# Simon_Says_Jump.net
KiCad netlist of a schematic drawn in EAGLE
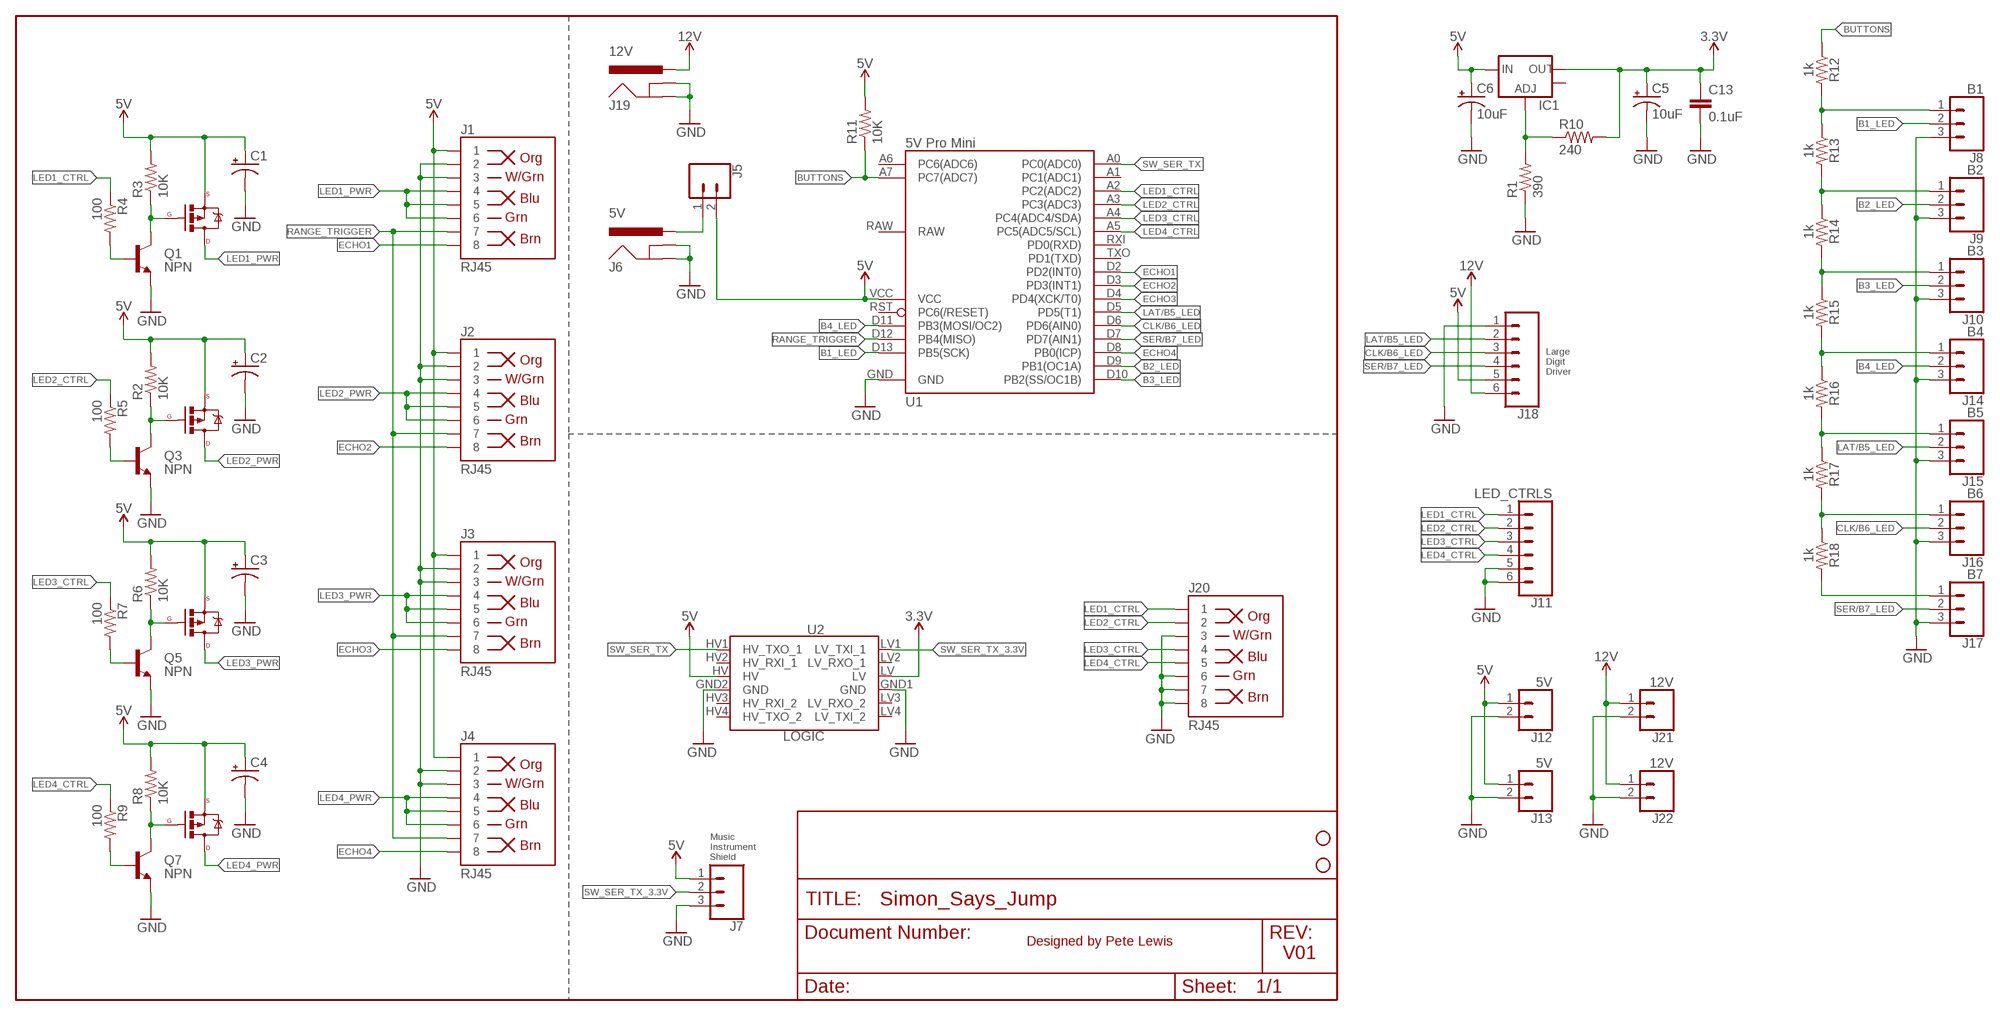
[diagram p0: schematic, sheet 1]

(export (version "E")
  (design (tool "Eeschema 10.0.6"))
  (components
    (comp (ref "C1")
      (value "CAP_POLCPOL-RADIAL-10UF-25V-KIT")
      (footprint "eagle-import:CPOL-RADIAL-10UF-25V-KIT")
      (libsource (lib "eagle-import") (part "CAP_POLCPOL-RADIAL-10UF-25V-KIT"))
    )
    (comp (ref "C2")
      (value "CAP_POLCPOL-RADIAL-10UF-25V-KIT")
      (footprint "eagle-import:CPOL-RADIAL-10UF-25V-KIT")
      (libsource (lib "eagle-import") (part "CAP_POLCPOL-RADIAL-10UF-25V-KIT"))
    )
    (comp (ref "C3")
      (value "CAP_POLCPOL-RADIAL-10UF-25V-KIT")
      (footprint "eagle-import:CPOL-RADIAL-10UF-25V-KIT")
      (libsource (lib "eagle-import") (part "CAP_POLCPOL-RADIAL-10UF-25V-KIT"))
    )
    (comp (ref "C4")
      (value "CAP_POLCPOL-RADIAL-10UF-25V-KIT")
      (footprint "eagle-import:CPOL-RADIAL-10UF-25V-KIT")
      (libsource (lib "eagle-import") (part "CAP_POLCPOL-RADIAL-10UF-25V-KIT"))
    )
    (comp (ref "C5")
      (value "10uF")
      (footprint "eagle-import:EIA3216")
      (libsource (lib "eagle-import") (part "CAP_POL1206"))
    )
    (comp (ref "C6")
      (value "10uF")
      (footprint "eagle-import:EIA3216")
      (libsource (lib "eagle-import") (part "CAP_POL1206"))
    )
    (comp (ref "C13")
      (value "0.1uF")
      (footprint "eagle-import:0603-CAP")
      (libsource (lib "eagle-import") (part "CAP0603-CAP"))
    )
    (comp (ref "IC1")
      (value "V_REG_LM1117SOT223")
      (footprint "eagle-import:SOT223")
      (libsource (lib "eagle-import") (part "V_REG_LM1117SOT223"))
    )
    (comp (ref "J1")
      (value "RJ45")
      (footprint "eagle-import:RJ45-8")
      (libsource (lib "eagle-import") (part "RJ45-8"))
    )
    (comp (ref "J2")
      (value "RJ45")
      (footprint "eagle-import:RJ45-8")
      (libsource (lib "eagle-import") (part "RJ45-8"))
    )
    (comp (ref "J3")
      (value "RJ45")
      (footprint "eagle-import:RJ45-8")
      (libsource (lib "eagle-import") (part "RJ45-8"))
    )
    (comp (ref "J4")
      (value "RJ45")
      (footprint "eagle-import:RJ45-8")
      (libsource (lib "eagle-import") (part "RJ45-8"))
    )
    (comp (ref "J5")
      (value "CONN_02PTH3")
      (footprint "eagle-import:1X02_LONGPADS")
      (libsource (lib "eagle-import") (part "CONN_02PTH3"))
    )
    (comp (ref "J6")
      (value "5V")
      (footprint "eagle-import:POWER_JACK_PTH_LOCK")
      (libsource (lib "eagle-import") (part "POWER_JACKPTH_LOCK"))
    )
    (comp (ref "J7")
      (value "CONN_03LONGPADS")
      (footprint "eagle-import:1X03_LONGPADS")
      (libsource (lib "eagle-import") (part "CONN_03LONGPADS"))
    )
    (comp (ref "J8")
      (value "B1")
      (footprint "eagle-import:1X03_LONGPADS")
      (libsource (lib "eagle-import") (part "CONN_03LONGPADS"))
    )
    (comp (ref "J9")
      (value "B2")
      (footprint "eagle-import:1X03_LONGPADS")
      (libsource (lib "eagle-import") (part "CONN_03LONGPADS"))
    )
    (comp (ref "J10")
      (value "B3")
      (footprint "eagle-import:1X03_LONGPADS")
      (libsource (lib "eagle-import") (part "CONN_03LONGPADS"))
    )
    (comp (ref "J11")
      (value "LED_CTRLS")
      (footprint "eagle-import:1X06_LONGPADS")
      (libsource (lib "eagle-import") (part "CONN_06LONGPADS"))
    )
    (comp (ref "J12")
      (value "5V")
      (footprint "eagle-import:1X02_LONGPADS")
      (libsource (lib "eagle-import") (part "CONN_02PTH3"))
    )
    (comp (ref "J13")
      (value "5V")
      (footprint "eagle-import:1X02_LONGPADS")
      (libsource (lib "eagle-import") (part "CONN_02PTH3"))
    )
    (comp (ref "J14")
      (value "B4")
      (footprint "eagle-import:1X03_LONGPADS")
      (libsource (lib "eagle-import") (part "CONN_03LONGPADS"))
    )
    (comp (ref "J15")
      (value "B5")
      (footprint "eagle-import:1X03_LONGPADS")
      (libsource (lib "eagle-import") (part "CONN_03LONGPADS"))
    )
    (comp (ref "J16")
      (value "B6")
      (footprint "eagle-import:1X03_LONGPADS")
      (libsource (lib "eagle-import") (part "CONN_03LONGPADS"))
    )
    (comp (ref "J17")
      (value "B7")
      (footprint "eagle-import:1X03_LONGPADS")
      (libsource (lib "eagle-import") (part "CONN_03LONGPADS"))
    )
    (comp (ref "J18")
      (value "CONN_06LONGPADS")
      (footprint "eagle-import:1X06_LONGPADS")
      (libsource (lib "eagle-import") (part "CONN_06LONGPADS"))
    )
    (comp (ref "J19")
      (value "12V")
      (footprint "eagle-import:POWER_JACK_PTH_LOCK")
      (libsource (lib "eagle-import") (part "POWER_JACKPTH_LOCK"))
    )
    (comp (ref "J20")
      (value "RJ45")
      (footprint "eagle-import:RJ45-8")
      (libsource (lib "eagle-import") (part "RJ45-8"))
    )
    (comp (ref "J21")
      (value "12V")
      (footprint "eagle-import:1X02_LONGPADS")
      (libsource (lib "eagle-import") (part "CONN_02PTH3"))
    )
    (comp (ref "J22")
      (value "12V")
      (footprint "eagle-import:1X02_LONGPADS")
      (libsource (lib "eagle-import") (part "CONN_02PTH3"))
    )
    (comp (ref "JP1")
      (value "STAND-OFFTIGHTER")
      (footprint "eagle-import:STAND-OFF-TIGHTER")
      (libsource (lib "eagle-import") (part "STAND-OFFTIGHTER"))
    )
    (comp (ref "JP7")
      (value "STAND-OFFTIGHTER")
      (footprint "eagle-import:STAND-OFF-TIGHTER")
      (libsource (lib "eagle-import") (part "STAND-OFFTIGHTER"))
    )
    (comp (ref "Q1")
      (value "NPN")
      (footprint "eagle-import:SOT23")
      (libsource (lib "eagle-import") (part "TRANSISTOR_NPNSOT23"))
    )
    (comp (ref "Q2")
      (value "P-Channel MOSFET")
      (footprint "eagle-import:TO220V")
      (libsource (lib "eagle-import") (part "MOSFET-PCHANNELPTH"))
    )
    (comp (ref "Q3")
      (value "NPN")
      (footprint "eagle-import:SOT23")
      (libsource (lib "eagle-import") (part "TRANSISTOR_NPNSOT23"))
    )
    (comp (ref "Q4")
      (value "P-Channel MOSFET")
      (footprint "eagle-import:TO220V")
      (libsource (lib "eagle-import") (part "MOSFET-PCHANNELPTH"))
    )
    (comp (ref "Q5")
      (value "NPN")
      (footprint "eagle-import:SOT23")
      (libsource (lib "eagle-import") (part "TRANSISTOR_NPNSOT23"))
    )
    (comp (ref "Q6")
      (value "P-Channel MOSFET")
      (footprint "eagle-import:TO220V")
      (libsource (lib "eagle-import") (part "MOSFET-PCHANNELPTH"))
    )
    (comp (ref "Q7")
      (value "NPN")
      (footprint "eagle-import:SOT23")
      (libsource (lib "eagle-import") (part "TRANSISTOR_NPNSOT23"))
    )
    (comp (ref "Q8")
      (value "P-Channel MOSFET")
      (footprint "eagle-import:TO220V")
      (libsource (lib "eagle-import") (part "MOSFET-PCHANNELPTH"))
    )
    (comp (ref "R1")
      (value "390")
      (footprint "eagle-import:0603-RES")
      (libsource (lib "eagle-import") (part "RESISTOR0603-RES"))
    )
    (comp (ref "R2")
      (value "10K")
      (footprint "eagle-import:0603-RES")
      (libsource (lib "eagle-import") (part "RESISTOR0603-RES"))
    )
    (comp (ref "R3")
      (value "10K")
      (footprint "eagle-import:0603-RES")
      (libsource (lib "eagle-import") (part "RESISTOR0603-RES"))
    )
    (comp (ref "R4")
      (value "100")
      (footprint "eagle-import:0603-RES")
      (libsource (lib "eagle-import") (part "RESISTOR0603-RES"))
    )
    (comp (ref "R5")
      (value "100")
      (footprint "eagle-import:0603-RES")
      (libsource (lib "eagle-import") (part "RESISTOR0603-RES"))
    )
    (comp (ref "R6")
      (value "10K")
      (footprint "eagle-import:0603-RES")
      (libsource (lib "eagle-import") (part "RESISTOR0603-RES"))
    )
    (comp (ref "R7")
      (value "100")
      (footprint "eagle-import:0603-RES")
      (libsource (lib "eagle-import") (part "RESISTOR0603-RES"))
    )
    (comp (ref "R8")
      (value "10K")
      (footprint "eagle-import:0603-RES")
      (libsource (lib "eagle-import") (part "RESISTOR0603-RES"))
    )
    (comp (ref "R9")
      (value "100")
      (footprint "eagle-import:0603-RES")
      (libsource (lib "eagle-import") (part "RESISTOR0603-RES"))
    )
    (comp (ref "R10")
      (value "240")
      (footprint "eagle-import:0603-RES")
      (libsource (lib "eagle-import") (part "RESISTOR0603-RES"))
    )
    (comp (ref "R11")
      (value "10K")
      (footprint "eagle-import:0603-RES")
      (libsource (lib "eagle-import") (part "RESISTOR0603-RES"))
    )
    (comp (ref "R12")
      (value "1k")
      (footprint "eagle-import:0603")
      (libsource (lib "eagle-import") (part "1KOHM-0603-1/10W-1%"))
    )
    (comp (ref "R13")
      (value "1k")
      (footprint "eagle-import:0603")
      (libsource (lib "eagle-import") (part "1KOHM-0603-1/10W-1%"))
    )
    (comp (ref "R14")
      (value "1k")
      (footprint "eagle-import:0603")
      (libsource (lib "eagle-import") (part "1KOHM-0603-1/10W-1%"))
    )
    (comp (ref "R15")
      (value "1k")
      (footprint "eagle-import:0603")
      (libsource (lib "eagle-import") (part "1KOHM-0603-1/10W-1%"))
    )
    (comp (ref "R16")
      (value "1k")
      (footprint "eagle-import:0603")
      (libsource (lib "eagle-import") (part "1KOHM-0603-1/10W-1%"))
    )
    (comp (ref "R17")
      (value "1k")
      (footprint "eagle-import:0603")
      (libsource (lib "eagle-import") (part "1KOHM-0603-1/10W-1%"))
    )
    (comp (ref "R18")
      (value "1k")
      (footprint "eagle-import:0603")
      (libsource (lib "eagle-import") (part "1KOHM-0603-1/10W-1%"))
    )
    (comp (ref "U1")
      (value "5V Pro Mini")
      (footprint "eagle-import:ARDUINO_PRO_MINI-V13_DIP")
      (libsource (lib "eagle-import") (part "ARDUINO_PRO_MINI-V13-DIP"))
    )
    (comp (ref "U2")
      (value "LOGIC")
      (footprint "eagle-import:SPARKFUN_LOGIC_LEVEL_CONVERTER")
      (libsource (lib "eagle-import") (part "SPARKFUN_LOGIC_LEVEL_CONVERTER"))
    )
  )
  (nets
    (net (code "1") (name "3.3V") (class "Default")
      (node (ref "C13") (pin "1") (pinfunction "1_1") (pintype "passive"))
      (node (ref "C5") (pin "A") (pinfunction "+_A") (pintype "passive"))
      (node (ref "IC1") (pin "2") (pinfunction "OUT_2") (pintype "output"))
      (node (ref "R10") (pin "2") (pinfunction "2_2") (pintype "passive"))
      (node (ref "U2") (pin "LV") (pinfunction "LV_LV") (pintype "power_in"))
    )
    (net (code "2") (name "5V") (class "Default")
      (node (ref "C1") (pin "1") (pinfunction "+_1") (pintype "passive"))
      (node (ref "C2") (pin "1") (pinfunction "+_1") (pintype "passive"))
      (node (ref "C3") (pin "1") (pinfunction "+_1") (pintype "passive"))
      (node (ref "C4") (pin "1") (pinfunction "+_1") (pintype "passive"))
      (node (ref "C6") (pin "A") (pinfunction "+_A") (pintype "passive"))
      (node (ref "IC1") (pin "3") (pinfunction "IN_3") (pintype "input"))
      (node (ref "J1") (pin "1") (pinfunction "1_1") (pintype "bidirectional"))
      (node (ref "J12") (pin "1") (pinfunction "1_1") (pintype "passive"))
      (node (ref "J13") (pin "1") (pinfunction "1_1") (pintype "passive"))
      (node (ref "J18") (pin "5") (pinfunction "5_5") (pintype "passive"))
      (node (ref "J2") (pin "1") (pinfunction "1_1") (pintype "bidirectional"))
      (node (ref "J3") (pin "1") (pinfunction "1_1") (pintype "bidirectional"))
      (node (ref "J4") (pin "1") (pinfunction "1_1") (pintype "bidirectional"))
      (node (ref "J5") (pin "2") (pinfunction "2_2") (pintype "passive"))
      (node (ref "J7") (pin "1") (pinfunction "1_1") (pintype "passive"))
      (node (ref "Q2") (pin "3") (pinfunction "S_3") (pintype "passive"))
      (node (ref "Q4") (pin "3") (pinfunction "S_3") (pintype "passive"))
      (node (ref "Q6") (pin "3") (pinfunction "S_3") (pintype "passive"))
      (node (ref "Q8") (pin "3") (pinfunction "S_3") (pintype "passive"))
      (node (ref "R11") (pin "2") (pinfunction "2_2") (pintype "passive"))
      (node (ref "R2") (pin "2") (pinfunction "2_2") (pintype "passive"))
      (node (ref "R3") (pin "2") (pinfunction "2_2") (pintype "passive"))
      (node (ref "R6") (pin "2") (pinfunction "2_2") (pintype "passive"))
      (node (ref "R8") (pin "2") (pinfunction "2_2") (pintype "passive"))
      (node (ref "U1") (pin "VCC") (pinfunction "VCC_VCC") (pintype "bidirectional"))
      (node (ref "U2") (pin "HV") (pinfunction "HV_HV") (pintype "power_in"))
    )
    (net (code "3") (name "12V") (class "Default")
      (node (ref "J18") (pin "6") (pinfunction "6_6") (pintype "passive"))
      (node (ref "J19") (pin "PWR") (pinfunction "PWR_PWR") (pintype "bidirectional"))
      (node (ref "J21") (pin "1") (pinfunction "1_1") (pintype "passive"))
      (node (ref "J22") (pin "1") (pinfunction "1_1") (pintype "passive"))
    )
    (net (code "4") (name "B1_LED") (class "Default")
      (node (ref "J8") (pin "2") (pinfunction "2_2") (pintype "passive"))
      (node (ref "U1") (pin "D13") (pinfunction "PB5(SCK)_D13") (pintype "bidirectional"))
    )
    (net (code "5") (name "B2_LED") (class "Default")
      (node (ref "J9") (pin "2") (pinfunction "2_2") (pintype "passive"))
      (node (ref "U1") (pin "D9") (pinfunction "PB1(OC1A)_D9") (pintype "bidirectional"))
    )
    (net (code "6") (name "B3_LED") (class "Default")
      (node (ref "J10") (pin "2") (pinfunction "2_2") (pintype "passive"))
      (node (ref "U1") (pin "D10") (pinfunction "PB2(SS/OC1B)_D10") (pintype "bidirectional"))
    )
    (net (code "7") (name "B4_LED") (class "Default")
      (node (ref "J14") (pin "2") (pinfunction "2_2") (pintype "passive"))
      (node (ref "U1") (pin "D11") (pinfunction "PB3(MOSI/OC2)_D11") (pintype "bidirectional"))
    )
    (net (code "8") (name "BUTTONS") (class "Default")
      (node (ref "R11") (pin "1") (pinfunction "1_1") (pintype "passive"))
      (node (ref "R12") (pin "1") (pinfunction "1_1") (pintype "passive"))
      (node (ref "U1") (pin "A7") (pinfunction "PC7(ADC7)_A7") (pintype "bidirectional"))
    )
    (net (code "9") (name "CLK{slash}B6_LED") (class "Default")
      (node (ref "J16") (pin "2") (pinfunction "2_2") (pintype "passive"))
      (node (ref "J18") (pin "3") (pinfunction "3_3") (pintype "passive"))
      (node (ref "U1") (pin "D6") (pinfunction "PD6(AIN0)_D6") (pintype "bidirectional"))
    )
    (net (code "10") (name "ECHO1") (class "Default")
      (node (ref "J1") (pin "8") (pinfunction "8_8") (pintype "bidirectional"))
      (node (ref "U1") (pin "D2") (pinfunction "PD2(INT0)_D2") (pintype "bidirectional"))
    )
    (net (code "11") (name "ECHO2") (class "Default")
      (node (ref "J2") (pin "8") (pinfunction "8_8") (pintype "bidirectional"))
      (node (ref "U1") (pin "D3") (pinfunction "PD3(INT1)_D3") (pintype "bidirectional"))
    )
    (net (code "12") (name "ECHO3") (class "Default")
      (node (ref "J3") (pin "8") (pinfunction "8_8") (pintype "bidirectional"))
      (node (ref "U1") (pin "D4") (pinfunction "PD4(XCK/T0)_D4") (pintype "bidirectional"))
    )
    (net (code "13") (name "ECHO4") (class "Default")
      (node (ref "J4") (pin "8") (pinfunction "8_8") (pintype "bidirectional"))
      (node (ref "U1") (pin "D8") (pinfunction "PB0(ICP)_D8") (pintype "bidirectional"))
    )
    (net (code "14") (name "GND") (class "Default")
      (node (ref "C1") (pin "2") (pinfunction "-_2") (pintype "passive"))
      (node (ref "C13") (pin "2") (pinfunction "2_2") (pintype "passive"))
      (node (ref "C2") (pin "2") (pinfunction "-_2") (pintype "passive"))
      (node (ref "C3") (pin "2") (pinfunction "-_2") (pintype "passive"))
      (node (ref "C4") (pin "2") (pinfunction "-_2") (pintype "passive"))
      (node (ref "C5") (pin "C") (pinfunction "-_C") (pintype "passive"))
      (node (ref "C6") (pin "C") (pinfunction "-_C") (pintype "passive"))
      (node (ref "J1") (pin "2") (pinfunction "2_2") (pintype "bidirectional"))
      (node (ref "J1") (pin "3") (pinfunction "3_3") (pintype "bidirectional"))
      (node (ref "J10") (pin "3") (pinfunction "3_3") (pintype "passive"))
      (node (ref "J11") (pin "5") (pinfunction "5_5") (pintype "passive"))
      (node (ref "J11") (pin "6") (pinfunction "6_6") (pintype "passive"))
      (node (ref "J12") (pin "2") (pinfunction "2_2") (pintype "passive"))
      (node (ref "J13") (pin "2") (pinfunction "2_2") (pintype "passive"))
      (node (ref "J14") (pin "3") (pinfunction "3_3") (pintype "passive"))
      (node (ref "J15") (pin "3") (pinfunction "3_3") (pintype "passive"))
      (node (ref "J16") (pin "3") (pinfunction "3_3") (pintype "passive"))
      (node (ref "J17") (pin "3") (pinfunction "3_3") (pintype "passive"))
      (node (ref "J18") (pin "1") (pinfunction "1_1") (pintype "passive"))
      (node (ref "J19") (pin "GND") (pinfunction "GND_GND") (pintype "bidirectional"))
      (node (ref "J19") (pin "GNDBREAK") (pinfunction "GNDBREAK_GNDBREAK") (pintype "bidirectional"))
      (node (ref "J2") (pin "2") (pinfunction "2_2") (pintype "bidirectional"))
      (node (ref "J2") (pin "3") (pinfunction "3_3") (pintype "bidirectional"))
      (node (ref "J20") (pin "3") (pinfunction "3_3") (pintype "bidirectional"))
      (node (ref "J20") (pin "6") (pinfunction "6_6") (pintype "bidirectional"))
      (node (ref "J20") (pin "7") (pinfunction "7_7") (pintype "bidirectional"))
      (node (ref "J20") (pin "8") (pinfunction "8_8") (pintype "bidirectional"))
      (node (ref "J21") (pin "2") (pinfunction "2_2") (pintype "passive"))
      (node (ref "J22") (pin "2") (pinfunction "2_2") (pintype "passive"))
      (node (ref "J3") (pin "2") (pinfunction "2_2") (pintype "bidirectional"))
      (node (ref "J3") (pin "3") (pinfunction "3_3") (pintype "bidirectional"))
      (node (ref "J4") (pin "2") (pinfunction "2_2") (pintype "bidirectional"))
      (node (ref "J4") (pin "3") (pinfunction "3_3") (pintype "bidirectional"))
      (node (ref "J6") (pin "GND") (pinfunction "GND_GND") (pintype "bidirectional"))
      (node (ref "J6") (pin "GNDBREAK") (pinfunction "GNDBREAK_GNDBREAK") (pintype "bidirectional"))
      (node (ref "J7") (pin "3") (pinfunction "3_3") (pintype "passive"))
      (node (ref "J8") (pin "3") (pinfunction "3_3") (pintype "passive"))
      (node (ref "J9") (pin "3") (pinfunction "3_3") (pintype "passive"))
      (node (ref "Q1") (pin "2") (pinfunction "E_2") (pintype "passive"))
      (node (ref "Q3") (pin "2") (pinfunction "E_2") (pintype "passive"))
      (node (ref "Q5") (pin "2") (pinfunction "E_2") (pintype "passive"))
      (node (ref "Q7") (pin "2") (pinfunction "E_2") (pintype "passive"))
      (node (ref "R1") (pin "1") (pinfunction "1_1") (pintype "passive"))
      (node (ref "U1") (pin "GND") (pinfunction "GND_GND") (pintype "bidirectional"))
      (node (ref "U2") (pin "GND1") (pinfunction "GND_GND1") (pintype "power_in"))
      (node (ref "U2") (pin "GND2") (pinfunction "GND_GND2") (pintype "power_in"))
    )
    (net (code "15") (name "LAT{slash}B5_LED") (class "Default")
      (node (ref "J15") (pin "2") (pinfunction "2_2") (pintype "passive"))
      (node (ref "J18") (pin "2") (pinfunction "2_2") (pintype "passive"))
      (node (ref "U1") (pin "D5") (pinfunction "PD5(T1)_D5") (pintype "bidirectional"))
    )
    (net (code "16") (name "LED1_CTRL") (class "Default")
      (node (ref "J11") (pin "1") (pinfunction "1_1") (pintype "passive"))
      (node (ref "J20") (pin "1") (pinfunction "1_1") (pintype "bidirectional"))
      (node (ref "R4") (pin "1") (pinfunction "1_1") (pintype "passive"))
      (node (ref "U1") (pin "A2") (pinfunction "PC2(ADC2)_A2") (pintype "bidirectional"))
    )
    (net (code "17") (name "LED1_PWR") (class "Default")
      (node (ref "J1") (pin "4") (pinfunction "4_4") (pintype "bidirectional"))
      (node (ref "J1") (pin "5") (pinfunction "5_5") (pintype "bidirectional"))
      (node (ref "J1") (pin "6") (pinfunction "6_6") (pintype "bidirectional"))
      (node (ref "Q2") (pin "2") (pinfunction "D_2") (pintype "passive"))
    )
    (net (code "18") (name "LED2_CTRL") (class "Default")
      (node (ref "J11") (pin "2") (pinfunction "2_2") (pintype "passive"))
      (node (ref "J20") (pin "2") (pinfunction "2_2") (pintype "bidirectional"))
      (node (ref "R5") (pin "1") (pinfunction "1_1") (pintype "passive"))
      (node (ref "U1") (pin "A3") (pinfunction "PC3(ADC3)_A3") (pintype "bidirectional"))
    )
    (net (code "19") (name "LED2_PWR") (class "Default")
      (node (ref "J2") (pin "4") (pinfunction "4_4") (pintype "bidirectional"))
      (node (ref "J2") (pin "5") (pinfunction "5_5") (pintype "bidirectional"))
      (node (ref "J2") (pin "6") (pinfunction "6_6") (pintype "bidirectional"))
      (node (ref "Q4") (pin "2") (pinfunction "D_2") (pintype "passive"))
    )
    (net (code "20") (name "LED3_CTRL") (class "Default")
      (node (ref "J11") (pin "3") (pinfunction "3_3") (pintype "passive"))
      (node (ref "J20") (pin "4") (pinfunction "4_4") (pintype "bidirectional"))
      (node (ref "R7") (pin "1") (pinfunction "1_1") (pintype "passive"))
      (node (ref "U1") (pin "A4") (pinfunction "PC4(ADC4/SDA)_A4") (pintype "bidirectional"))
    )
    (net (code "21") (name "LED3_PWR") (class "Default")
      (node (ref "J3") (pin "4") (pinfunction "4_4") (pintype "bidirectional"))
      (node (ref "J3") (pin "5") (pinfunction "5_5") (pintype "bidirectional"))
      (node (ref "J3") (pin "6") (pinfunction "6_6") (pintype "bidirectional"))
      (node (ref "Q6") (pin "2") (pinfunction "D_2") (pintype "passive"))
    )
    (net (code "22") (name "LED4_CTRL") (class "Default")
      (node (ref "J11") (pin "4") (pinfunction "4_4") (pintype "passive"))
      (node (ref "J20") (pin "5") (pinfunction "5_5") (pintype "bidirectional"))
      (node (ref "R9") (pin "1") (pinfunction "1_1") (pintype "passive"))
      (node (ref "U1") (pin "A5") (pinfunction "PC5(ADC5/SCL)_A5") (pintype "bidirectional"))
    )
    (net (code "23") (name "LED4_PWR") (class "Default")
      (node (ref "J4") (pin "4") (pinfunction "4_4") (pintype "bidirectional"))
      (node (ref "J4") (pin "5") (pinfunction "5_5") (pintype "bidirectional"))
      (node (ref "J4") (pin "6") (pinfunction "6_6") (pintype "bidirectional"))
      (node (ref "Q8") (pin "2") (pinfunction "D_2") (pintype "passive"))
    )
    (net (code "24") (name "Net-(IC1-ADJ)") (class "Default")
      (node (ref "IC1") (pin "1") (pinfunction "ADJ_1") (pintype "input"))
      (node (ref "R1") (pin "2") (pinfunction "2_2") (pintype "passive"))
      (node (ref "R10") (pin "1") (pinfunction "1_1") (pintype "passive"))
    )
    (net (code "25") (name "Net-(J5-Pad1)") (class "Default")
      (node (ref "J5") (pin "1") (pinfunction "1_1") (pintype "passive"))
      (node (ref "J6") (pin "PWR") (pinfunction "PWR_PWR") (pintype "bidirectional"))
    )
    (net (code "26") (name "Net-(J8-Pad1)") (class "Default")
      (node (ref "J8") (pin "1") (pinfunction "1_1") (pintype "passive"))
      (node (ref "R12") (pin "2") (pinfunction "2_2") (pintype "passive"))
      (node (ref "R13") (pin "1") (pinfunction "1_1") (pintype "passive"))
    )
    (net (code "27") (name "Net-(J9-Pad1)") (class "Default")
      (node (ref "J9") (pin "1") (pinfunction "1_1") (pintype "passive"))
      (node (ref "R13") (pin "2") (pinfunction "2_2") (pintype "passive"))
      (node (ref "R14") (pin "1") (pinfunction "1_1") (pintype "passive"))
    )
    (net (code "28") (name "Net-(J10-Pad1)") (class "Default")
      (node (ref "J10") (pin "1") (pinfunction "1_1") (pintype "passive"))
      (node (ref "R14") (pin "2") (pinfunction "2_2") (pintype "passive"))
      (node (ref "R15") (pin "1") (pinfunction "1_1") (pintype "passive"))
    )
    (net (code "29") (name "Net-(J14-Pad1)") (class "Default")
      (node (ref "J14") (pin "1") (pinfunction "1_1") (pintype "passive"))
      (node (ref "R15") (pin "2") (pinfunction "2_2") (pintype "passive"))
      (node (ref "R16") (pin "1") (pinfunction "1_1") (pintype "passive"))
    )
    (net (code "30") (name "Net-(J15-Pad1)") (class "Default")
      (node (ref "J15") (pin "1") (pinfunction "1_1") (pintype "passive"))
      (node (ref "R16") (pin "2") (pinfunction "2_2") (pintype "passive"))
      (node (ref "R17") (pin "1") (pinfunction "1_1") (pintype "passive"))
    )
    (net (code "31") (name "Net-(J16-Pad1)") (class "Default")
      (node (ref "J16") (pin "1") (pinfunction "1_1") (pintype "passive"))
      (node (ref "R17") (pin "2") (pinfunction "2_2") (pintype "passive"))
      (node (ref "R18") (pin "1") (pinfunction "1_1") (pintype "passive"))
    )
    (net (code "32") (name "Net-(J17-Pad1)") (class "Default")
      (node (ref "J17") (pin "1") (pinfunction "1_1") (pintype "passive"))
      (node (ref "R18") (pin "2") (pinfunction "2_2") (pintype "passive"))
    )
    (net (code "33") (name "Net-(Q1-B)") (class "Default")
      (node (ref "Q1") (pin "1") (pinfunction "B_1") (pintype "passive"))
      (node (ref "R4") (pin "2") (pinfunction "2_2") (pintype "passive"))
    )
    (net (code "34") (name "Net-(Q1-C)") (class "Default")
      (node (ref "Q1") (pin "3") (pinfunction "C_3") (pintype "passive"))
      (node (ref "Q2") (pin "1") (pinfunction "G_1") (pintype "passive"))
      (node (ref "R3") (pin "1") (pinfunction "1_1") (pintype "passive"))
    )
    (net (code "35") (name "Net-(Q3-B)") (class "Default")
      (node (ref "Q3") (pin "1") (pinfunction "B_1") (pintype "passive"))
      (node (ref "R5") (pin "2") (pinfunction "2_2") (pintype "passive"))
    )
    (net (code "36") (name "Net-(Q3-C)") (class "Default")
      (node (ref "Q3") (pin "3") (pinfunction "C_3") (pintype "passive"))
      (node (ref "Q4") (pin "1") (pinfunction "G_1") (pintype "passive"))
      (node (ref "R2") (pin "1") (pinfunction "1_1") (pintype "passive"))
    )
    (net (code "37") (name "Net-(Q5-B)") (class "Default")
      (node (ref "Q5") (pin "1") (pinfunction "B_1") (pintype "passive"))
      (node (ref "R7") (pin "2") (pinfunction "2_2") (pintype "passive"))
    )
    (net (code "38") (name "Net-(Q5-C)") (class "Default")
      (node (ref "Q5") (pin "3") (pinfunction "C_3") (pintype "passive"))
      (node (ref "Q6") (pin "1") (pinfunction "G_1") (pintype "passive"))
      (node (ref "R6") (pin "1") (pinfunction "1_1") (pintype "passive"))
    )
    (net (code "39") (name "Net-(Q7-B)") (class "Default")
      (node (ref "Q7") (pin "1") (pinfunction "B_1") (pintype "passive"))
      (node (ref "R9") (pin "2") (pinfunction "2_2") (pintype "passive"))
    )
    (net (code "40") (name "Net-(Q7-C)") (class "Default")
      (node (ref "Q7") (pin "3") (pinfunction "C_3") (pintype "passive"))
      (node (ref "Q8") (pin "1") (pinfunction "G_1") (pintype "passive"))
      (node (ref "R8") (pin "1") (pinfunction "1_1") (pintype "passive"))
    )
    (net (code "41") (name "RANGE_TRIGGER") (class "Default")
      (node (ref "J1") (pin "7") (pinfunction "7_7") (pintype "bidirectional"))
      (node (ref "J2") (pin "7") (pinfunction "7_7") (pintype "bidirectional"))
      (node (ref "J3") (pin "7") (pinfunction "7_7") (pintype "bidirectional"))
      (node (ref "J4") (pin "7") (pinfunction "7_7") (pintype "bidirectional"))
      (node (ref "U1") (pin "D12") (pinfunction "PB4(MISO)_D12") (pintype "bidirectional"))
    )
    (net (code "42") (name "SER{slash}B7_LED") (class "Default")
      (node (ref "J17") (pin "2") (pinfunction "2_2") (pintype "passive"))
      (node (ref "J18") (pin "4") (pinfunction "4_4") (pintype "passive"))
      (node (ref "U1") (pin "D7") (pinfunction "PD7(AIN1)_D7") (pintype "bidirectional"))
    )
    (net (code "43") (name "SW_SER_TX") (class "Default")
      (node (ref "U1") (pin "A0") (pinfunction "PC0(ADC0)_A0") (pintype "bidirectional"))
      (node (ref "U2") (pin "HV1") (pinfunction "HV_TXO_1_HV1") (pintype "bidirectional"))
    )
    (net (code "44") (name "SW_SER_TX_3.3V") (class "Default")
      (node (ref "J7") (pin "2") (pinfunction "2_2") (pintype "passive"))
      (node (ref "U2") (pin "LV1") (pinfunction "LV_TXI_1_LV1") (pintype "bidirectional"))
    )
    (net (code "45") (name "unconnected-(IC1-OUT-Pad4)") (class "Default")
      (node (ref "IC1") (pin "4") (pinfunction "OUT_4") (pintype "output"))
    )
    (net (code "46") (name "unconnected-(U1-PC1(ADC1)-PadA1)") (class "Default")
      (node (ref "U1") (pin "A1") (pinfunction "PC1(ADC1)_A1") (pintype "bidirectional"))
    )
    (net (code "47") (name "unconnected-(U1-PC6(ADC6)-PadA6)") (class "Default")
      (node (ref "U1") (pin "A6") (pinfunction "PC6(ADC6)_A6") (pintype "bidirectional"))
    )
    (net (code "48") (name "unconnected-(U1-PC6({slash}RESET)-PadRST)") (class "Default")
      (node (ref "U1") (pin "RST") (pinfunction "PC6(/RESET)_RST") (pintype "bidirectional"))
    )
    (net (code "49") (name "unconnected-(U1-PD0(RXD)-PadRXI)") (class "Default")
      (node (ref "U1") (pin "RXI") (pinfunction "PD0(RXD)_RXI") (pintype "bidirectional"))
    )
    (net (code "50") (name "unconnected-(U1-PD1(TXD)-PadTXO)") (class "Default")
      (node (ref "U1") (pin "TXO") (pinfunction "PD1(TXD)_TXO") (pintype "bidirectional"))
    )
    (net (code "51") (name "unconnected-(U1-PadRAW)") (class "Default")
      (node (ref "U1") (pin "RAW") (pinfunction "RAW_RAW") (pintype "bidirectional"))
    )
    (net (code "52") (name "unconnected-(U2-HV_RXI_1-PadHV2)") (class "Default")
      (node (ref "U2") (pin "HV2") (pinfunction "HV_RXI_1_HV2") (pintype "bidirectional"))
    )
    (net (code "53") (name "unconnected-(U2-HV_RXI_2-PadHV3)") (class "Default")
      (node (ref "U2") (pin "HV3") (pinfunction "HV_RXI_2_HV3") (pintype "bidirectional"))
    )
    (net (code "54") (name "unconnected-(U2-HV_TXO_2-PadHV4)") (class "Default")
      (node (ref "U2") (pin "HV4") (pinfunction "HV_TXO_2_HV4") (pintype "bidirectional"))
    )
    (net (code "55") (name "unconnected-(U2-LV_RXO_1-PadLV2)") (class "Default")
      (node (ref "U2") (pin "LV2") (pinfunction "LV_RXO_1_LV2") (pintype "bidirectional"))
    )
    (net (code "56") (name "unconnected-(U2-LV_RXO_2-PadLV3)") (class "Default")
      (node (ref "U2") (pin "LV3") (pinfunction "LV_RXO_2_LV3") (pintype "bidirectional"))
    )
    (net (code "57") (name "unconnected-(U2-LV_TXI_2-PadLV4)") (class "Default")
      (node (ref "U2") (pin "LV4") (pinfunction "LV_TXI_2_LV4") (pintype "bidirectional"))
    )
  )
)
